# schematic.net
KiCad netlist of a schematic drawn in EasyEDA
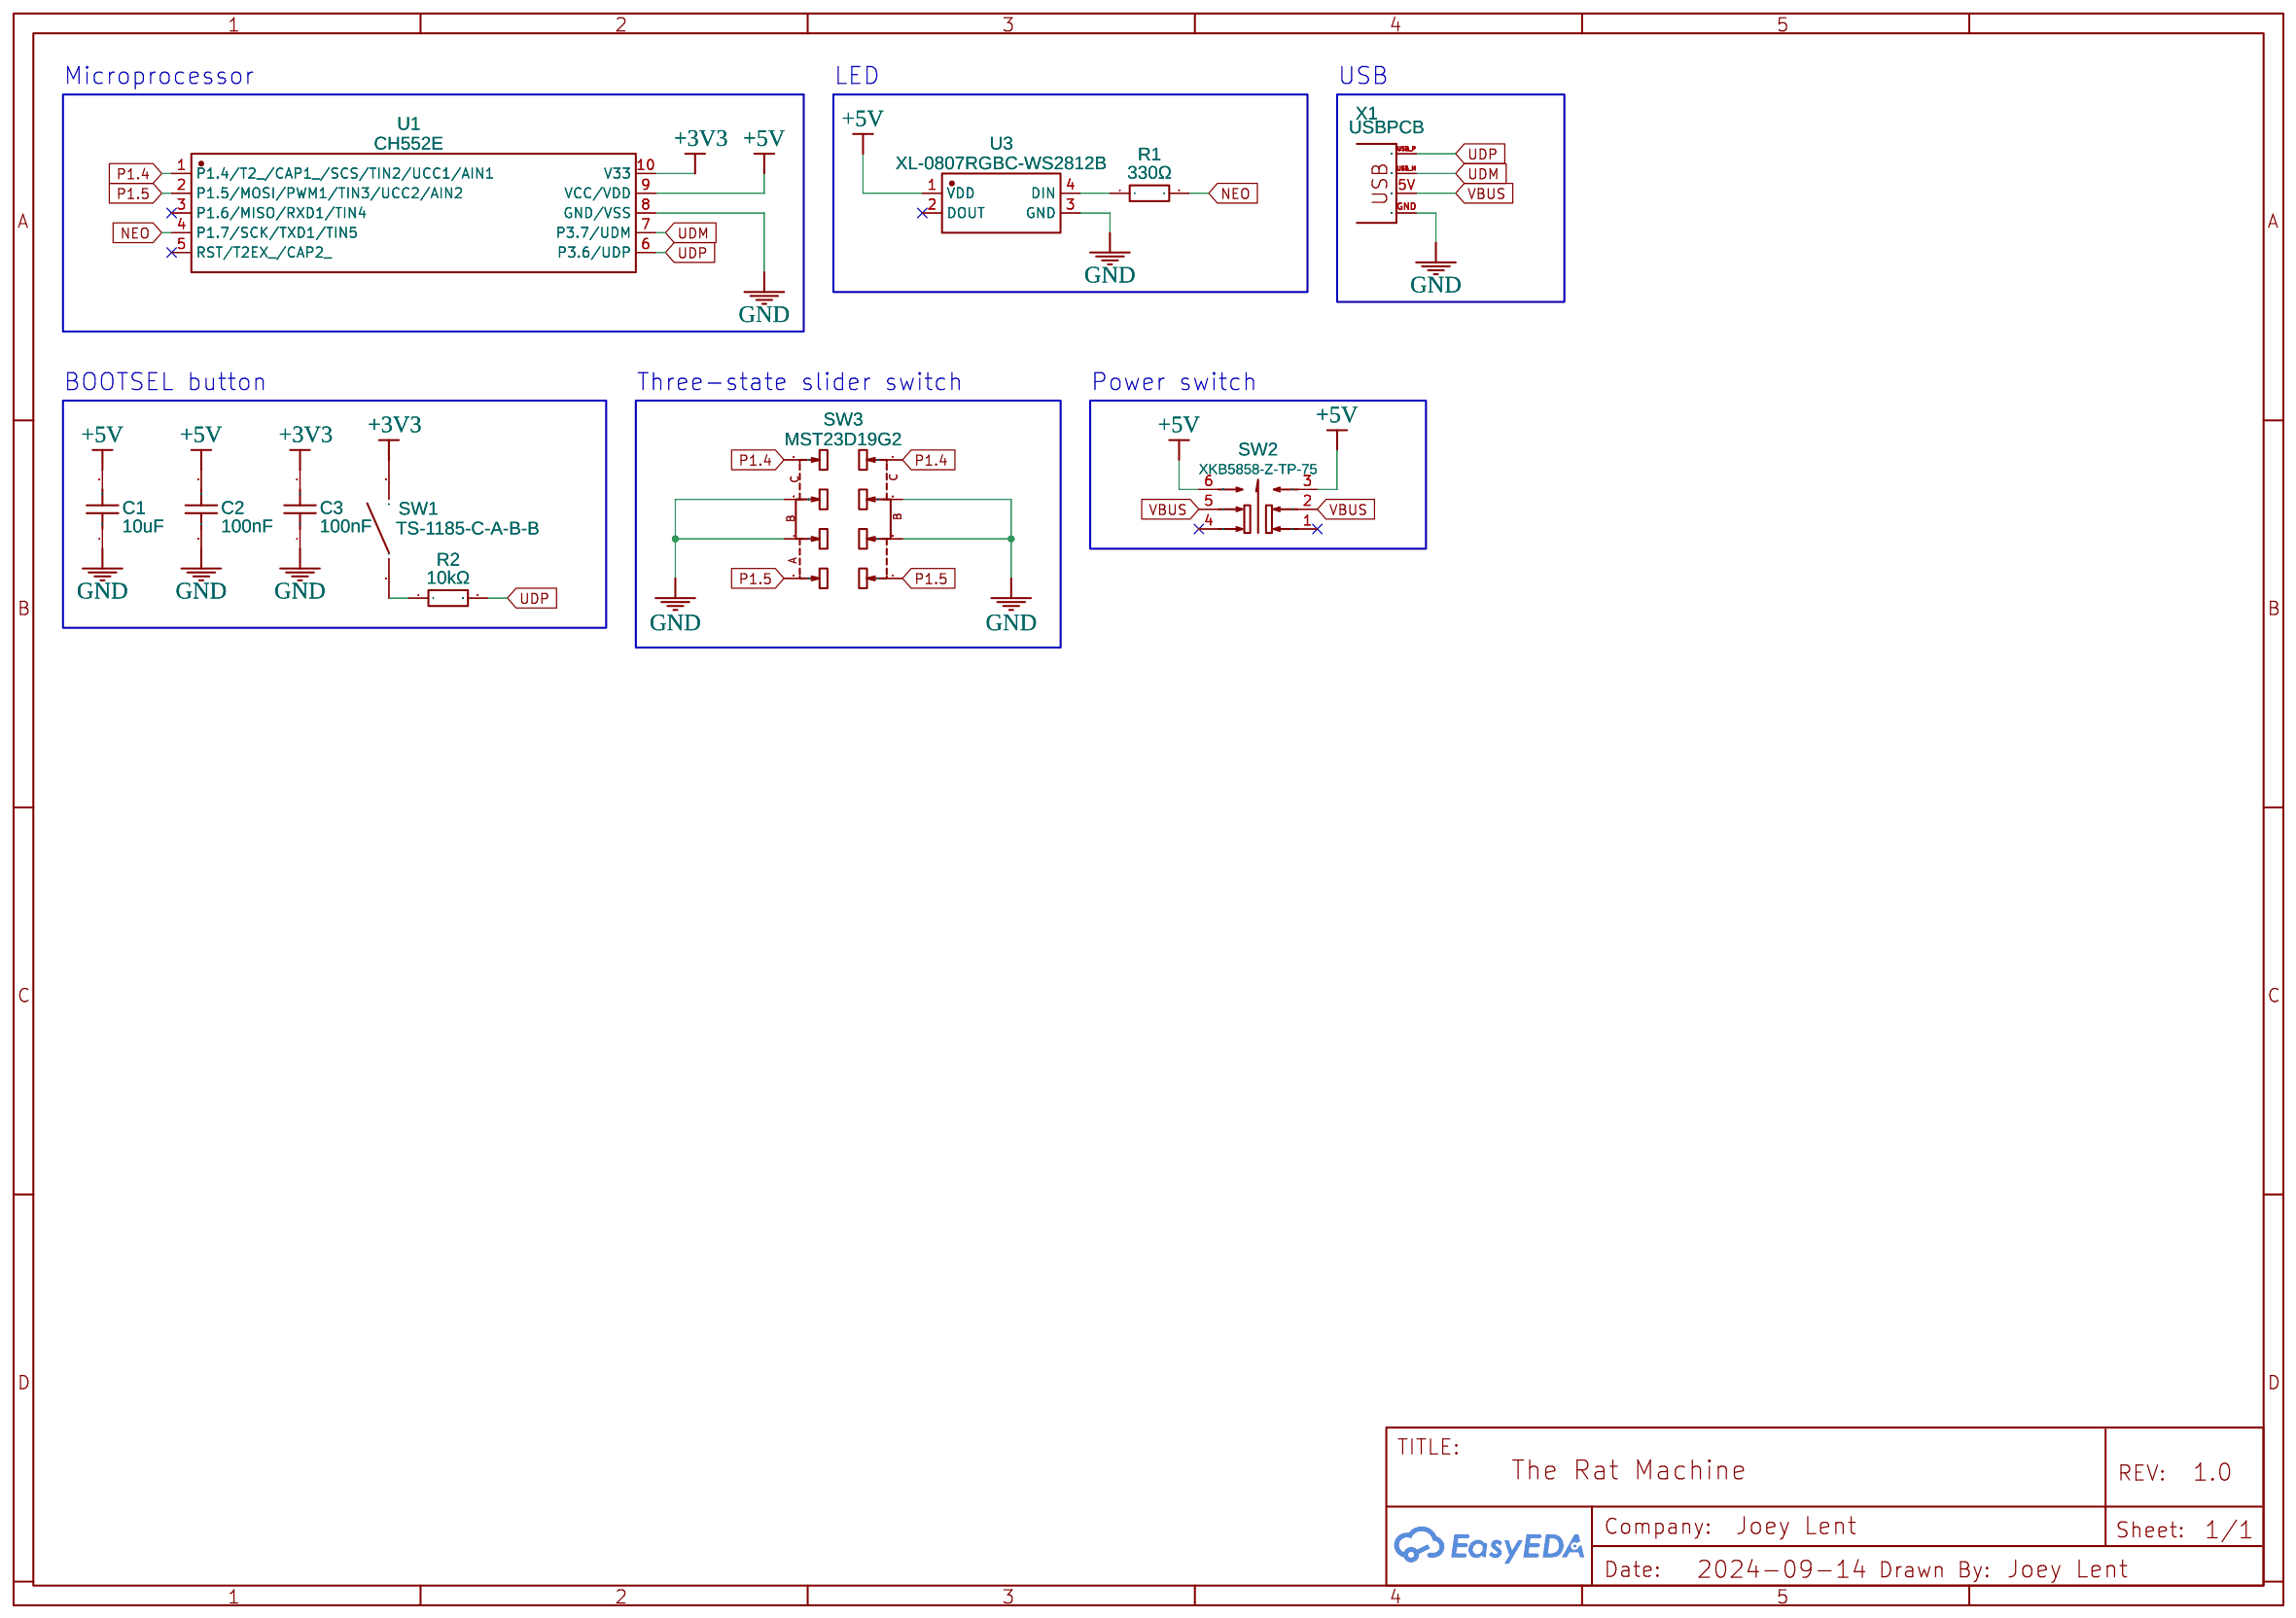
[diagram p0: schematic sheet]

(export (version "E")
  (design (tool "Eeschema 10.0.6"))
  (components
    (comp (ref "C1")
      (value "10uF")
      (fields
        (field (name "Manufacturer Part") "CL10A106KP8NNNC")
        (field (name "Manufacturer") "SAMSUNG(三星)")
      )
      (libsource (lib "") (part "CL10A106KP8NNNC"))
    )
    (comp (ref "C2")
      (value "100nF")
      (fields
        (field (name "Manufacturer Part") "CC0603KRX7R9BB104")
        (field (name "Manufacturer") "YAGEO(国巨)")
      )
      (libsource (lib "") (part "CC0603KRX7R9BB104"))
    )
    (comp (ref "C3")
      (value "100nF")
      (fields
        (field (name "Manufacturer Part") "CC0603KRX7R9BB104")
        (field (name "Manufacturer") "YAGEO(国巨)")
      )
      (libsource (lib "") (part "CC0603KRX7R9BB104"))
    )
    (comp (ref "R1")
      (value "330Ω")
      (fields
        (field (name "Manufacturer Part") "0603WAF3300T5E")
        (field (name "Manufacturer") "UNI-ROYAL(厚声)")
      )
      (libsource (lib "") (part "0603WAF3300T5E"))
    )
    (comp (ref "R2")
      (value "10kΩ")
      (fields
        (field (name "Manufacturer Part") "0603WAF1002T5E")
        (field (name "Manufacturer") "UNI-ROYAL(厚声)")
      )
      (libsource (lib "") (part "0603WAF1002T5E"))
    )
    (comp (ref "SW1")
      (value "TS-1185-C-A-B-B")
      (fields (field (name "Manufacturer") "XKB Connectivity(中国星坤)"))
      (libsource (lib "") (part "TS-1185-C-A-B-B"))
    )
    (comp (ref "SW2")
      (value "XKB5858-Z-TP-75")
      (fields (field (name "Manufacturer") "XKB Connectivity(中国星坤)"))
      (libsource (lib "") (part "XKB5858-Z-TP-75"))
    )
    (comp (ref "SW3")
      (value "MST23D19G2")
      (fields (field (name "Manufacturer") "SHOU HAN(首韩)"))
      (libsource (lib "") (part "MST23D19G2"))
    )
    (comp (ref "U1")
      (value "CH552E")
      (fields (field (name "Manufacturer") "WCH(南京沁恒)"))
      (libsource (lib "") (part "CH552E"))
    )
    (comp (ref "U3")
      (value "XL-0807RGBC-WS2812B")
      (fields (field (name "Manufacturer") "XINGLIGHT(成兴光)"))
      (libsource (lib "") (part "XL-0807RGBC-WS2812B"))
    )
    (comp (ref "X1") (value "USBPCB") (libsource (lib "") (part "USBPCB")))
  )
  (nets
    (net (code "1") (name "+3V3") (class "Default")
      (node (ref "C3") (pin "2") (pinfunction "2_2") (pintype "unspecified"))
      (node (ref "SW1") (pin "2") (pinfunction "2_2") (pintype "input"))
      (node (ref "U1") (pin "10") (pinfunction "V33_10") (pintype "unspecified"))
    )
    (net (code "2") (name "+5V") (class "Default")
      (node (ref "C1") (pin "2") (pinfunction "2_2") (pintype "unspecified"))
      (node (ref "C2") (pin "2") (pinfunction "2_2") (pintype "unspecified"))
      (node (ref "SW2") (pin "3") (pinfunction "3_3") (pintype "unspecified"))
      (node (ref "SW2") (pin "6") (pinfunction "6_6") (pintype "unspecified"))
      (node (ref "U1") (pin "9") (pinfunction "VCC/VDD_9") (pintype "unspecified"))
      (node (ref "U3") (pin "1") (pinfunction "VDD_1") (pintype "unspecified"))
    )
    (net (code "3") (name "GND") (class "Default")
      (node (ref "C1") (pin "1") (pinfunction "1_1") (pintype "unspecified"))
      (node (ref "C2") (pin "1") (pinfunction "1_1") (pintype "unspecified"))
      (node (ref "C3") (pin "1") (pinfunction "1_1") (pintype "unspecified"))
      (node (ref "SW3") (pin "2") (pinfunction "2_2") (pintype "unspecified"))
      (node (ref "SW3") (pin "3") (pinfunction "3_3") (pintype "unspecified"))
      (node (ref "SW3") (pin "6") (pinfunction "6_6") (pintype "unspecified"))
      (node (ref "SW3") (pin "7") (pinfunction "7_7") (pintype "unspecified"))
      (node (ref "U1") (pin "8") (pinfunction "GND/VSS_8") (pintype "unspecified"))
      (node (ref "U3") (pin "3") (pinfunction "GND_3") (pintype "unspecified"))
      (node (ref "X1") (pin "GND") (pinfunction "GND_GND") (pintype "bidirectional"))
    )
    (net (code "4") (name "NEO") (class "Default")
      (node (ref "R1") (pin "2") (pinfunction "2_2") (pintype "input"))
      (node (ref "U1") (pin "4") (pinfunction "P1.7/SCK/TXD1/TIN5_4") (pintype "unspecified"))
    )
    (net (code "5") (name "Net-(R2-Pad1)") (class "Default")
      (node (ref "R2") (pin "1") (pinfunction "1_1") (pintype "input"))
      (node (ref "SW1") (pin "1") (pinfunction "1_1") (pintype "input"))
    )
    (net (code "6") (name "Net-(U3-DIN)") (class "Default")
      (node (ref "R1") (pin "1") (pinfunction "1_1") (pintype "input"))
      (node (ref "U3") (pin "4") (pinfunction "DIN_4") (pintype "unspecified"))
    )
    (net (code "7") (name "P1.4") (class "Default")
      (node (ref "SW3") (pin "4") (pinfunction "4_4") (pintype "unspecified"))
      (node (ref "SW3") (pin "5") (pinfunction "5_5") (pintype "unspecified"))
      (node (ref "U1") (pin "1") (pinfunction "P1.4/T2_/CAP1_/SCS/TIN2/UCC1/AIN1_1") (pintype "unspecified"))
    )
    (net (code "8") (name "P1.5") (class "Default")
      (node (ref "SW3") (pin "1") (pinfunction "1_1") (pintype "unspecified"))
      (node (ref "SW3") (pin "8") (pinfunction "8_8") (pintype "unspecified"))
      (node (ref "U1") (pin "2") (pinfunction "P1.5/MOSI/PWM1/TIN3/UCC2/AIN2_2") (pintype "unspecified"))
    )
    (net (code "9") (name "UDM") (class "Default")
      (node (ref "U1") (pin "7") (pinfunction "P3.7/UDM_7") (pintype "unspecified"))
      (node (ref "X1") (pin "USB_M") (pinfunction "D-_USB_M") (pintype "bidirectional"))
    )
    (net (code "10") (name "UDP") (class "Default")
      (node (ref "R2") (pin "2") (pinfunction "2_2") (pintype "input"))
      (node (ref "U1") (pin "6") (pinfunction "P3.6/UDP_6") (pintype "unspecified"))
      (node (ref "X1") (pin "USB_P") (pinfunction "D+_USB_P") (pintype "bidirectional"))
    )
    (net (code "11") (name "VBUS") (class "Default")
      (node (ref "SW2") (pin "2") (pinfunction "2_2") (pintype "unspecified"))
      (node (ref "SW2") (pin "5") (pinfunction "5_5") (pintype "unspecified"))
      (node (ref "X1") (pin "5V") (pinfunction "VBUS_5V") (pintype "bidirectional"))
    )
    (net (code "12") (name "unconnected-(SW2-Pad1)") (class "Default")
      (node (ref "SW2") (pin "1") (pinfunction "1_1") (pintype "unspecified+no_connect"))
    )
    (net (code "13") (name "unconnected-(SW2-Pad4)") (class "Default")
      (node (ref "SW2") (pin "4") (pinfunction "4_4") (pintype "unspecified+no_connect"))
    )
    (net (code "14") (name "unconnected-(U1-P1.6{slash}MISO{slash}RXD1{slash}TIN4-Pad3)") (class "Default")
      (node (ref "U1") (pin "3") (pinfunction "P1.6/MISO/RXD1/TIN4_3") (pintype "unspecified+no_connect"))
    )
    (net (code "15") (name "unconnected-(U1-RST{slash}T2EX_{slash}CAP2_-Pad5)") (class "Default")
      (node (ref "U1") (pin "5") (pinfunction "RST/T2EX_/CAP2__5") (pintype "unspecified+no_connect"))
    )
    (net (code "16") (name "unconnected-(U3-DOUT-Pad2)") (class "Default")
      (node (ref "U3") (pin "2") (pinfunction "DOUT_2") (pintype "unspecified+no_connect"))
    )
  )
)
